# sb-sonata-usbphy.net
KiCad netlist of a schematic drawn in Altium Designer
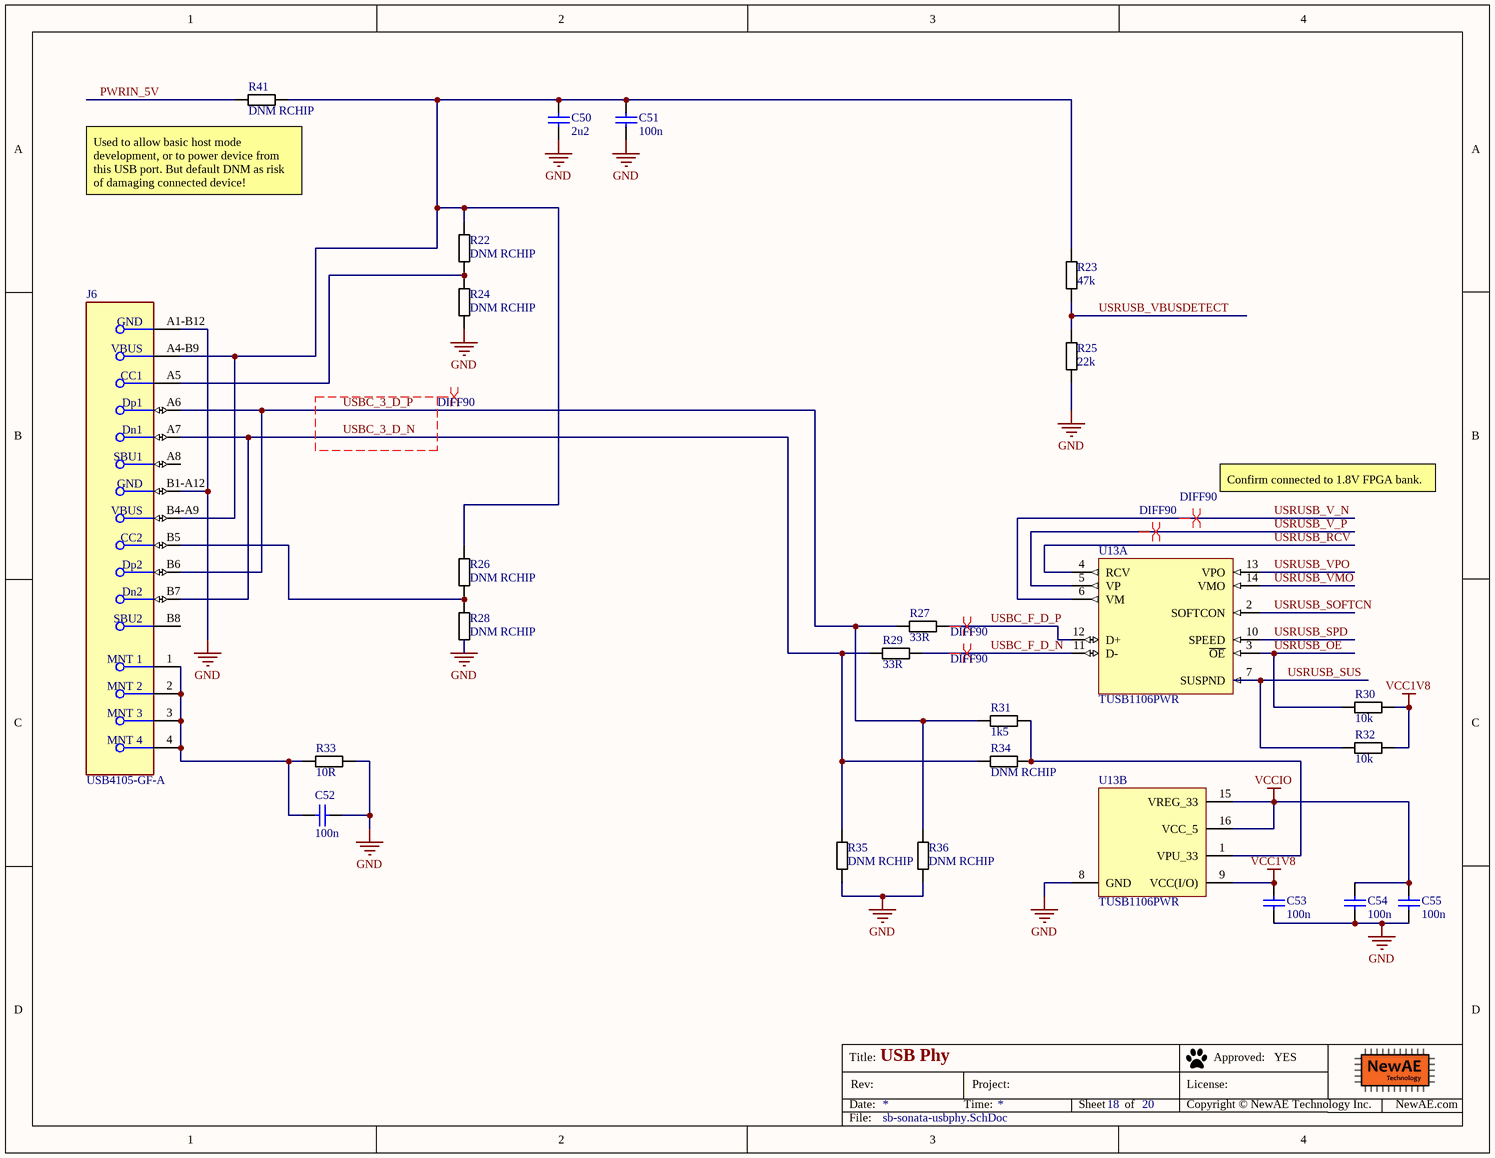
[diagram p0: sb-sonata-usbphy.SchDoc]

(export (version "E")
  (design (tool "Eeschema 10.0.6"))
  (components
    (comp (ref "C50")
      (value "2u2")
      (footprint "CAPC0603_M")
      (description "2u2, 0603")
      (fields (field (name "PART NUMBER") "CCHIP-2u2-0603"))
      (libsource (lib "NewAE_AltiumLib") (part "CAP"))
    )
    (comp (ref "C51")
      (value "100n")
      (footprint "CAPC0402_M")
      (description "100n, 0402")
      (fields (field (name "PART NUMBER") "CCHIP-100n-0402"))
      (libsource (lib "NewAE_AltiumLib") (part "CAP"))
    )
    (comp (ref "C52")
      (value "100n")
      (footprint "CAPC0603_M")
      (description "100n, 0603")
      (fields (field (name "PART NUMBER") "CCHIP-100n-0603"))
      (libsource (lib "NewAE_AltiumLib") (part "CAP"))
    )
    (comp (ref "C53")
      (value "100n")
      (footprint "CAPC0402_M")
      (description "100n, 0402")
      (fields (field (name "PART NUMBER") "CCHIP-100n-0402"))
      (libsource (lib "NewAE_AltiumLib") (part "CAP"))
    )
    (comp (ref "C54")
      (value "100n")
      (footprint "CAPC0402_M")
      (description "100n, 0402")
      (fields (field (name "PART NUMBER") "CCHIP-100n-0402"))
      (libsource (lib "NewAE_AltiumLib") (part "CAP"))
    )
    (comp (ref "C55")
      (value "100n")
      (footprint "CAPC0402_M")
      (description "100n, 0402")
      (fields (field (name "PART NUMBER") "CCHIP-100n-0402"))
      (libsource (lib "NewAE_AltiumLib") (part "CAP"))
    )
    (comp (ref "J6")
      (value "USB4105-GF-A")
      (footprint "FP-USB4105-GF-A-MFG")
      (description "CONN RCPT USB2.0 TYPEC 5A")
      (fields
        (field (name "MANUFACTURER") "GCT")
        (field (name "OCTOPART") "https://octopart.com/usb4105-gf-a-gct-106627878")
      )
      (libsource (lib "Altium Content Vault") (part "e7c17a616881a82b79941196b4bec10"))
    )
    (comp (ref "R22")
      (value "DNM RCHIP")
      (footprint "RESC1608X55N")
      (description "Do Not Mount Resistor")
      (fields (field (name "PART NUMBER") "RCHIP-DNM-0603"))
      (libsource (lib "NewAE_AltiumLib") (part "RES-EU"))
    )
    (comp (ref "R23")
      (value "47k")
      (footprint "RESC1005X40N")
      (description "47k res, 0402, 1%, 1/16W")
      (fields (field (name "PART NUMBER") "RCHIP-47K-0402") (field (name "TOLERANCE") "1%"))
      (libsource (lib "NewAE_AltiumLib") (part "RES-EU"))
    )
    (comp (ref "R24")
      (value "DNM RCHIP")
      (footprint "RESC1608X55N")
      (description "Do Not Mount Resistor")
      (fields (field (name "PART NUMBER") "RCHIP-DNM-0603"))
      (libsource (lib "NewAE_AltiumLib") (part "RES-EU"))
    )
    (comp (ref "R25")
      (value "22k")
      (footprint "RESC1005X40N")
      (description "22k res, 0402, 1%, 1/16W")
      (fields (field (name "PART NUMBER") "RCHIP-22K-0402") (field (name "TOLERANCE") "1%"))
      (libsource (lib "NewAE_AltiumLib") (part "RES-EU"))
    )
    (comp (ref "R26")
      (value "DNM RCHIP")
      (footprint "RESC1608X55N")
      (description "Do Not Mount Resistor")
      (fields (field (name "PART NUMBER") "RCHIP-DNM-0603"))
      (libsource (lib "NewAE_AltiumLib") (part "RES-EU"))
    )
    (comp (ref "R27")
      (value "33R")
      (footprint "RESC1608X55N")
      (description "33R res, 0603, 1%, 1/10W")
      (fields (field (name "PART NUMBER") "RCHIP-33R-0603") (field (name "TOLERANCE") "1%"))
      (libsource (lib "") (part "RES-EU_1"))
    )
    (comp (ref "R28")
      (value "DNM RCHIP")
      (footprint "RESC1608X55N")
      (description "Do Not Mount Resistor")
      (fields (field (name "PART NUMBER") "RCHIP-DNM-0603"))
      (libsource (lib "NewAE_AltiumLib") (part "RES-EU"))
    )
    (comp (ref "R29")
      (value "33R")
      (footprint "RESC1608X55N")
      (description "33R res, 0603, 1%, 1/10W")
      (fields (field (name "PART NUMBER") "RCHIP-33R-0603") (field (name "TOLERANCE") "1%"))
      (libsource (lib "") (part "RES-EU_1"))
    )
    (comp (ref "R30")
      (value "10k")
      (footprint "RESC1005X40N")
      (description "10k res, 0402, 1%, 1/16W")
      (fields (field (name "PART NUMBER") "RCHIP-10K-0402") (field (name "TOLERANCE") "1%"))
      (libsource (lib "") (part "RES-EU_1"))
    )
    (comp (ref "R31")
      (value "1k5")
      (footprint "RESC1608X55N")
      (description "1k5 res, 0603, 1%, 1/10W")
      (fields (field (name "PART NUMBER") "RCHIP-1K5-0603") (field (name "TOLERANCE") "1%"))
      (libsource (lib "") (part "RES-EU_1"))
    )
    (comp (ref "R32")
      (value "10k")
      (footprint "RESC1005X40N")
      (description "10k res, 0402, 1%, 1/16W")
      (fields (field (name "PART NUMBER") "RCHIP-10K-0402") (field (name "TOLERANCE") "1%"))
      (libsource (lib "") (part "RES-EU_1"))
    )
    (comp (ref "R33")
      (value "10R")
      (footprint "RESC1608X55N")
      (description "10R res, 0603, 1%, 1/10W")
      (fields (field (name "PART NUMBER") "RCHIP-10R-0603") (field (name "TOLERANCE") "1%"))
      (libsource (lib "") (part "RES-EU_1"))
    )
    (comp (ref "R34")
      (value "DNM RCHIP")
      (footprint "RESC1608X55N")
      (description "Do Not Mount Resistor")
      (fields (field (name "PART NUMBER") "RCHIP-DNM-0603"))
      (libsource (lib "") (part "RES-EU_1"))
    )
    (comp (ref "R35")
      (value "DNM RCHIP")
      (footprint "RESC1608X55N")
      (description "Do Not Mount Resistor")
      (fields (field (name "PART NUMBER") "RCHIP-DNM-0603"))
      (libsource (lib "") (part "RES-EU_2"))
    )
    (comp (ref "R36")
      (value "DNM RCHIP")
      (footprint "RESC1608X55N")
      (description "Do Not Mount Resistor")
      (fields (field (name "PART NUMBER") "RCHIP-DNM-0603"))
      (libsource (lib "") (part "RES-EU_2"))
    )
    (comp (ref "R41")
      (value "DNM RCHIP")
      (footprint "RESC1608X55N")
      (description "Do Not Mount Resistor")
      (fields (field (name "PART NUMBER") "RCHIP-DNM-0603"))
      (libsource (lib "") (part "RES-EU_3"))
    )
    (comp (ref "U13")
      (value "TUSB1106PWR")
      (footprint "PW0016A_L")
      (fields (field (name "MANUFACTURER") "Texas Instruments"))
      (libsource (lib "Altium Content Vault") (part "TI-TUSB1106-TSSOP_PW-16"))
    )
  )
  (nets
    (net (code "1") (name "/PWRIN_5V") (class "Default")
      (node (ref "R41") (pin "2") (pinfunction "2_2") (pintype "passive"))
    )
    (net (code "2") (name "/USBC_3_D_N") (class "Default")
      (node (ref "J6") (pin "A7") (pinfunction "Dn1_A7") (pintype "bidirectional"))
      (node (ref "J6") (pin "B7") (pinfunction "Dn2_B7") (pintype "bidirectional"))
      (node (ref "R29") (pin "1") (pinfunction "1_1") (pintype "passive"))
      (node (ref "R34") (pin "1") (pinfunction "1_1") (pintype "passive"))
      (node (ref "R35") (pin "2") (pinfunction "2_2") (pintype "passive"))
    )
    (net (code "3") (name "/USBC_3_D_P") (class "Default")
      (node (ref "J6") (pin "A6") (pinfunction "Dp1_A6") (pintype "bidirectional"))
      (node (ref "J6") (pin "B6") (pinfunction "Dp2_B6") (pintype "bidirectional"))
      (node (ref "R27") (pin "1") (pinfunction "1_1") (pintype "passive"))
      (node (ref "R31") (pin "1") (pinfunction "1_1") (pintype "passive"))
      (node (ref "R36") (pin "2") (pinfunction "2_2") (pintype "passive"))
    )
    (net (code "4") (name "/USBC_F_D_N") (class "Default")
      (node (ref "R29") (pin "2") (pinfunction "2_2") (pintype "passive"))
      (node (ref "U13") (pin "11") (pinfunction "D-_11") (pintype "bidirectional"))
    )
    (net (code "5") (name "/USBC_F_D_P") (class "Default")
      (node (ref "R27") (pin "2") (pinfunction "2_2") (pintype "passive"))
      (node (ref "U13") (pin "12") (pinfunction "D+_12") (pintype "bidirectional"))
    )
    (net (code "6") (name "/USRUSB_OE") (class "Default")
      (node (ref "R30") (pin "1") (pinfunction "1_1") (pintype "passive"))
      (node (ref "U13") (pin "3") (pinfunction "~{OE}_3") (pintype "input"))
    )
    (net (code "7") (name "/USRUSB_RCV") (class "Default")
      (node (ref "U13") (pin "4") (pinfunction "RCV_4") (pintype "output"))
    )
    (net (code "8") (name "/USRUSB_SOFTCN") (class "Default")
      (node (ref "U13") (pin "2") (pinfunction "SOFTCON_2") (pintype "input"))
    )
    (net (code "9") (name "/USRUSB_SPD") (class "Default")
      (node (ref "U13") (pin "10") (pinfunction "SPEED_10") (pintype "input"))
    )
    (net (code "10") (name "/USRUSB_SUS") (class "Default")
      (node (ref "R32") (pin "1") (pinfunction "1_1") (pintype "passive"))
      (node (ref "U13") (pin "7") (pinfunction "SUSPND_7") (pintype "input"))
    )
    (net (code "11") (name "/USRUSB_VBUSDETECT") (class "Default")
      (node (ref "R23") (pin "2") (pinfunction "2_2") (pintype "passive"))
      (node (ref "R25") (pin "1") (pinfunction "1_1") (pintype "passive"))
    )
    (net (code "12") (name "/USRUSB_VMO") (class "Default")
      (node (ref "U13") (pin "14") (pinfunction "VMO_14") (pintype "input"))
    )
    (net (code "13") (name "/USRUSB_VPO") (class "Default")
      (node (ref "U13") (pin "13") (pinfunction "VPO_13") (pintype "input"))
    )
    (net (code "14") (name "/USRUSB_V_N") (class "Default")
      (node (ref "U13") (pin "6") (pinfunction "VM_6") (pintype "output"))
    )
    (net (code "15") (name "/USRUSB_V_P") (class "Default")
      (node (ref "U13") (pin "5") (pinfunction "VP_5") (pintype "output"))
    )
    (net (code "16") (name "GND") (class "Default")
      (node (ref "C50") (pin "2") (pinfunction "2_2") (pintype "passive"))
      (node (ref "C51") (pin "2") (pinfunction "2_2") (pintype "passive"))
      (node (ref "C52") (pin "2") (pinfunction "2_2") (pintype "passive"))
      (node (ref "C53") (pin "2") (pinfunction "2_2") (pintype "passive"))
      (node (ref "C54") (pin "2") (pinfunction "2_2") (pintype "passive"))
      (node (ref "C55") (pin "2") (pinfunction "2_2") (pintype "passive"))
      (node (ref "J6") (pin "A1-B12") (pinfunction "GND_A1-B12") (pintype "power_in"))
      (node (ref "J6") (pin "B1-A12") (pinfunction "GND_B1-A12") (pintype "bidirectional"))
      (node (ref "R24") (pin "2") (pinfunction "2_2") (pintype "passive"))
      (node (ref "R25") (pin "2") (pinfunction "2_2") (pintype "passive"))
      (node (ref "R28") (pin "2") (pinfunction "2_2") (pintype "passive"))
      (node (ref "R33") (pin "2") (pinfunction "2_2") (pintype "passive"))
      (node (ref "R35") (pin "1") (pinfunction "1_1") (pintype "passive"))
      (node (ref "R36") (pin "1") (pinfunction "1_1") (pintype "passive"))
      (node (ref "U13") (pin "8") (pinfunction "GND_8") (pintype "power_in"))
    )
    (net (code "17") (name "Net-(C50-Pad1)") (class "Default")
      (node (ref "C50") (pin "1") (pinfunction "1_1") (pintype "passive"))
      (node (ref "C51") (pin "1") (pinfunction "1_1") (pintype "passive"))
      (node (ref "J6") (pin "A4-B9") (pinfunction "VBUS_A4-B9") (pintype "power_in"))
      (node (ref "J6") (pin "B4-A9") (pinfunction "VBUS_B4-A9") (pintype "bidirectional"))
      (node (ref "R22") (pin "1") (pinfunction "1_1") (pintype "passive"))
      (node (ref "R23") (pin "1") (pinfunction "1_1") (pintype "passive"))
      (node (ref "R26") (pin "1") (pinfunction "1_1") (pintype "passive"))
      (node (ref "R41") (pin "1") (pinfunction "1_1") (pintype "passive"))
    )
    (net (code "18") (name "Net-(J6-CC1)") (class "Default")
      (node (ref "J6") (pin "A5") (pinfunction "CC1_A5") (pintype "power_in"))
      (node (ref "R22") (pin "2") (pinfunction "2_2") (pintype "passive"))
      (node (ref "R24") (pin "1") (pinfunction "1_1") (pintype "passive"))
    )
    (net (code "19") (name "Net-(J6-CC2)") (class "Default")
      (node (ref "J6") (pin "B5") (pinfunction "CC2_B5") (pintype "bidirectional"))
      (node (ref "R26") (pin "2") (pinfunction "2_2") (pintype "passive"))
      (node (ref "R28") (pin "1") (pinfunction "1_1") (pintype "passive"))
    )
    (net (code "20") (name "Net-(J6-MNT_1)") (class "Default")
      (node (ref "C52") (pin "1") (pinfunction "1_1") (pintype "passive"))
      (node (ref "J6") (pin "1") (pinfunction "MNT_1_1") (pintype "power_in"))
      (node (ref "J6") (pin "2") (pinfunction "MNT_2_2") (pintype "power_in"))
      (node (ref "J6") (pin "3") (pinfunction "MNT_3_3") (pintype "power_in"))
      (node (ref "J6") (pin "4") (pinfunction "MNT_4_4") (pintype "power_in"))
      (node (ref "R33") (pin "1") (pinfunction "1_1") (pintype "passive"))
    )
    (net (code "21") (name "Net-(U13B-VPU_33)") (class "Default")
      (node (ref "R31") (pin "2") (pinfunction "2_2") (pintype "passive"))
      (node (ref "R34") (pin "2") (pinfunction "2_2") (pintype "passive"))
      (node (ref "U13") (pin "1") (pinfunction "VPU_33_1") (pintype "power_in"))
    )
    (net (code "22") (name "VCC1V8") (class "Default")
      (node (ref "C53") (pin "1") (pinfunction "1_1") (pintype "passive"))
      (node (ref "R30") (pin "2") (pinfunction "2_2") (pintype "passive"))
      (node (ref "R32") (pin "2") (pinfunction "2_2") (pintype "passive"))
      (node (ref "U13") (pin "9") (pinfunction "VCC(I/O)_9") (pintype "power_in"))
    )
    (net (code "23") (name "VCCIO") (class "Default")
      (node (ref "C54") (pin "1") (pinfunction "1_1") (pintype "passive"))
      (node (ref "C55") (pin "1") (pinfunction "1_1") (pintype "passive"))
      (node (ref "U13") (pin "15") (pinfunction "VREG_33_15") (pintype "power_in"))
      (node (ref "U13") (pin "16") (pinfunction "VCC_5_16") (pintype "power_in"))
    )
    (net (code "24") (name "unconnected-(J6-SBU1-PadA8)") (class "Default")
      (node (ref "J6") (pin "A8") (pinfunction "SBU1_A8") (pintype "bidirectional"))
    )
    (net (code "25") (name "unconnected-(J6-SBU2-PadB8)") (class "Default")
      (node (ref "J6") (pin "B8") (pinfunction "SBU2_B8") (pintype "power_in"))
    )
  )
)
